# QCopterFC_USB_Sch.net
KiCad netlist of a schematic drawn in Altium Designer
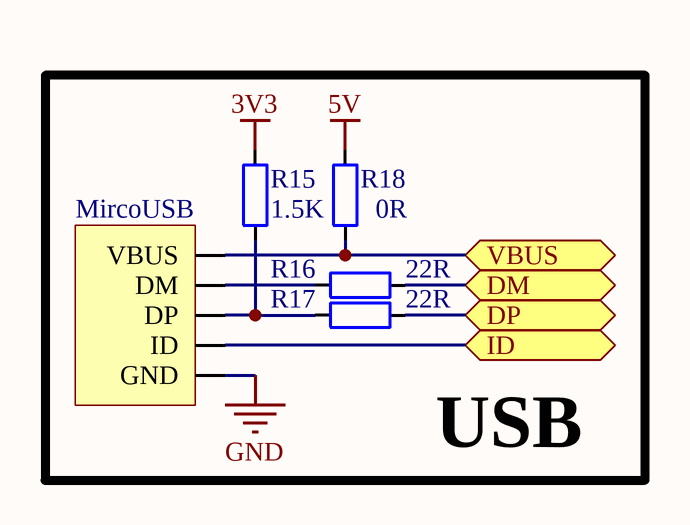
[diagram p0: QCopterFC_USB_Sch.SchDoc]

(export (version "E")
  (design (tool "Eeschema 10.0.6"))
  (components
    (comp (ref "MircoUSB")
      (value "USB_Micro")
      (footprint "PCB_USB:USB_Micro-AB")
      (description "USB")
      (libsource (lib "SCH_USB") (part "USB_Micro"))
    )
    (comp (ref "R15")
      (value "1.5K")
      (footprint "PCB_Passive:RES_0603")
      (description "Resistor")
      (fields (field (name "Comment") "Res_0603"))
      (libsource (lib "SCH_Passive") (part "Res_0603"))
    )
    (comp (ref "R16")
      (value "22R")
      (footprint "PCB_Passive:RES_0603")
      (description "Resistor")
      (fields (field (name "Comment") "Res_0603"))
      (libsource (lib "") (part "Res_0603_1"))
    )
    (comp (ref "R17")
      (value "22R")
      (footprint "PCB_Passive:RES_0603")
      (description "Resistor")
      (fields (field (name "Comment") "Res_0603"))
      (libsource (lib "") (part "Res_0603_1"))
    )
    (comp (ref "R18")
      (value "0R")
      (footprint "PCB_Passive:RES_0603")
      (description "Resistor")
      (fields (field (name "Comment") "Res_0603"))
      (libsource (lib "SCH_Passive") (part "Res_0603"))
    )
  )
  (nets
    (net (code "1") (name "/DM") (class "Default")
      (node (ref "R16") (pin "1") (pinfunction "1_1") (pintype "passive"))
    )
    (net (code "2") (name "/DP") (class "Default")
      (node (ref "R17") (pin "1") (pinfunction "1_1") (pintype "passive"))
    )
    (net (code "3") (name "/ID") (class "Default")
      (node (ref "MircoUSB") (pin "4") (pinfunction "ID_4") (pintype "passive"))
    )
    (net (code "4") (name "/VBUS") (class "Default")
      (node (ref "MircoUSB") (pin "1") (pinfunction "VBUS_1") (pintype "passive"))
      (node (ref "R18") (pin "1") (pinfunction "1_1") (pintype "passive"))
    )
    (net (code "5") (name "3V3") (class "Default")
      (node (ref "R15") (pin "2") (pinfunction "2_2") (pintype "passive"))
    )
    (net (code "6") (name "5V") (class "Default")
      (node (ref "R18") (pin "2") (pinfunction "2_2") (pintype "passive"))
    )
    (net (code "7") (name "GND") (class "Default")
      (node (ref "MircoUSB") (pin "5") (pinfunction "GND_5") (pintype "passive"))
    )
    (net (code "8") (name "Net-(MircoUSB-DM)") (class "Default")
      (node (ref "MircoUSB") (pin "2") (pinfunction "DM_2") (pintype "passive"))
      (node (ref "R16") (pin "2") (pinfunction "2_2") (pintype "passive"))
    )
    (net (code "9") (name "Net-(MircoUSB-DP)") (class "Default")
      (node (ref "MircoUSB") (pin "3") (pinfunction "DP_3") (pintype "passive"))
      (node (ref "R15") (pin "1") (pinfunction "1_1") (pintype "passive"))
      (node (ref "R17") (pin "2") (pinfunction "2_2") (pintype "passive"))
    )
  )
)
